# Schematic_Candy_sensor.net
KiCad netlist of a schematic drawn in EAGLE
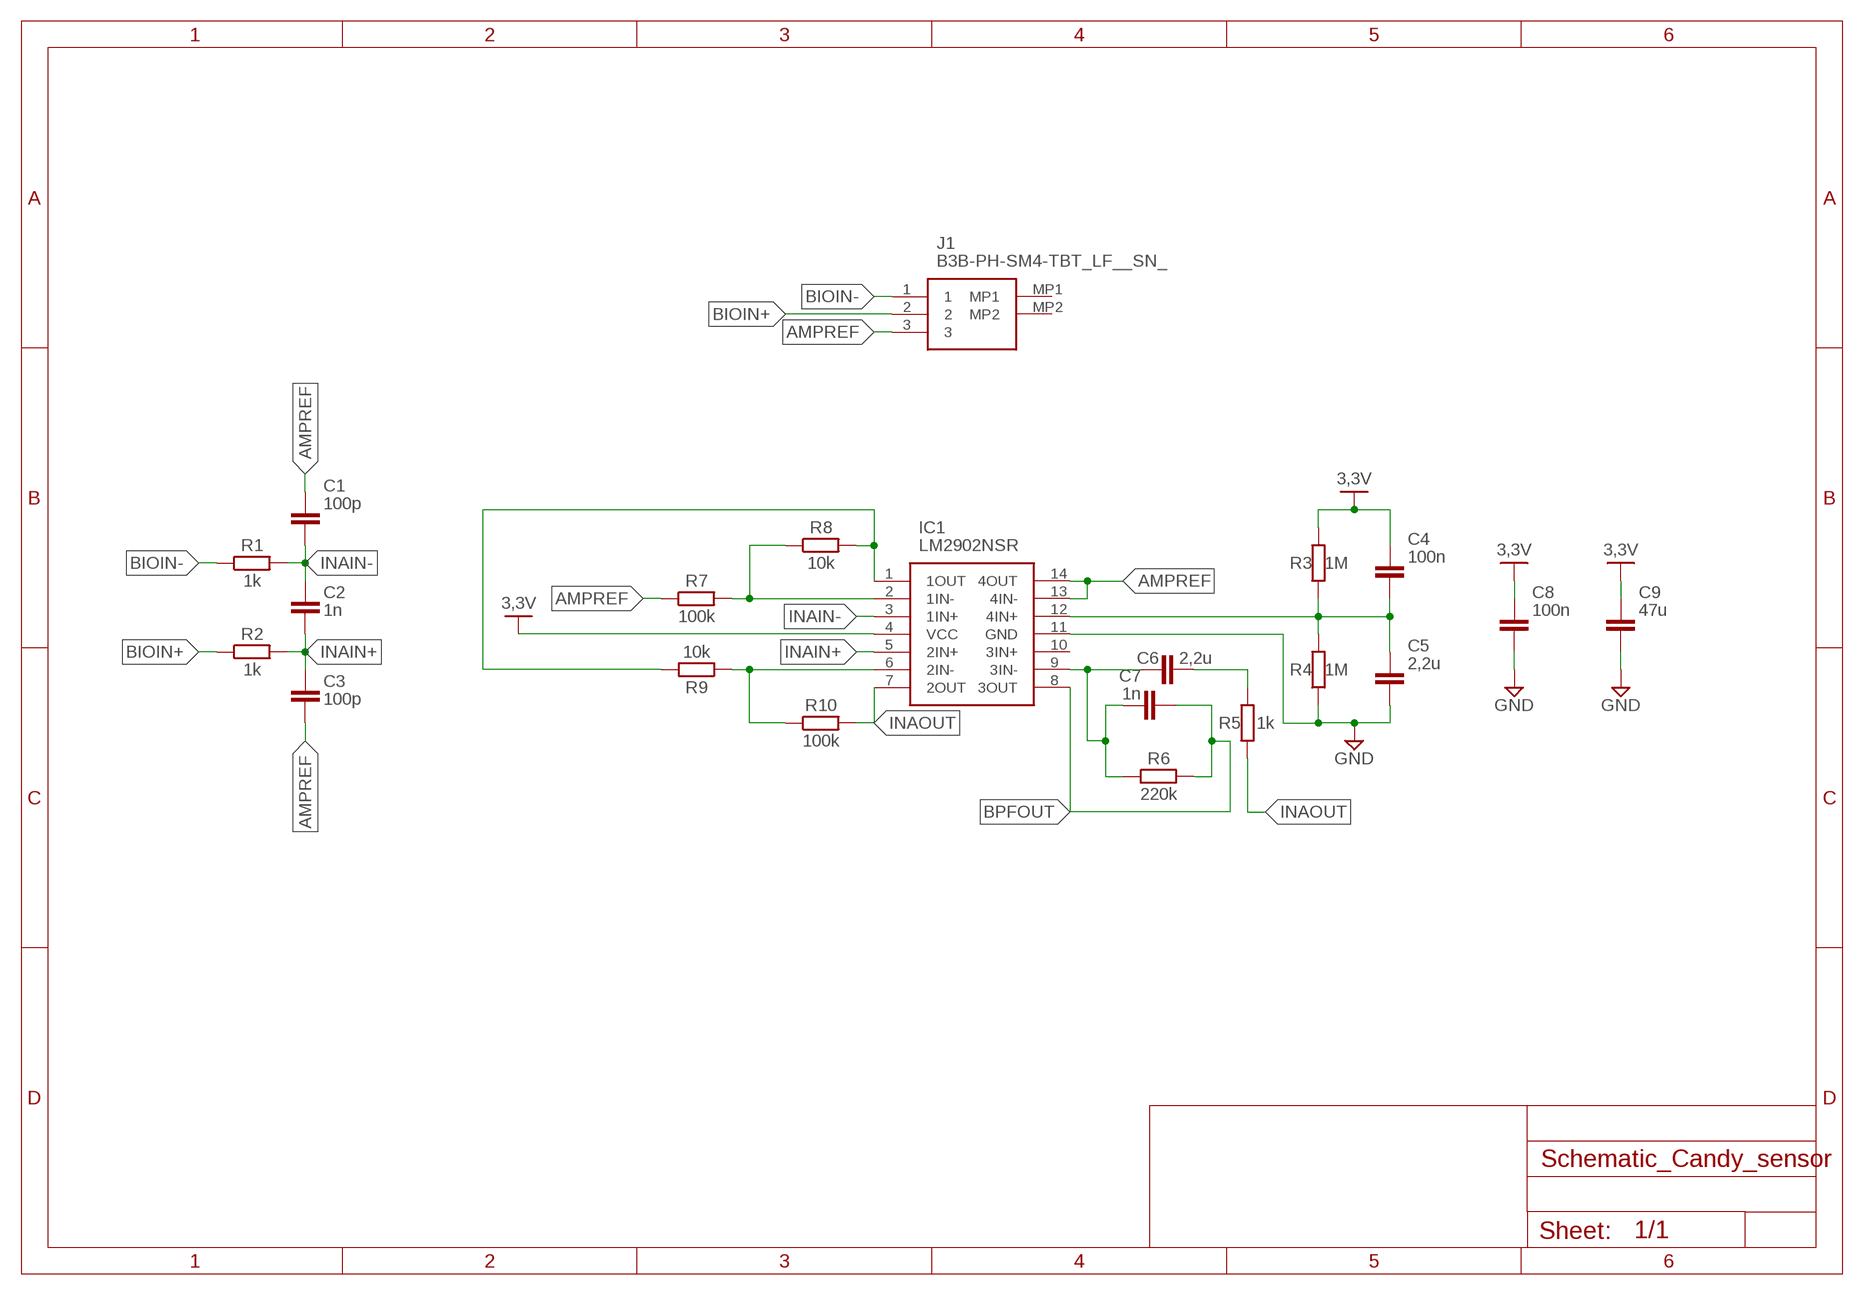
[diagram p0: schematic, sheet 1]

(export (version "E")
  (design (tool "Eeschema 10.0.6"))
  (components
    (comp (ref "C1")
      (value "100p")
      (footprint "eagle-import:CAPC2012X110")
      (libsource (lib "eagle-import") (part "CCHIP-0805(2012-METRIC)_"))
    )
    (comp (ref "C2")
      (value "1n")
      (footprint "eagle-import:CAPC2012X110")
      (libsource (lib "eagle-import") (part "CCHIP-0805(2012-METRIC)_"))
    )
    (comp (ref "C3")
      (value "100p")
      (footprint "eagle-import:CAPC2012X110")
      (libsource (lib "eagle-import") (part "CCHIP-0805(2012-METRIC)_"))
    )
    (comp (ref "C4")
      (value "100n")
      (footprint "eagle-import:CAPC2012X110")
      (libsource (lib "eagle-import") (part "CCHIP-0805(2012-METRIC)_"))
    )
    (comp (ref "C5")
      (value "2,2u")
      (footprint "eagle-import:CAPC2012X110")
      (libsource (lib "eagle-import") (part "CCHIP-0805(2012-METRIC)_"))
    )
    (comp (ref "C6")
      (value "2,2u")
      (footprint "eagle-import:CAPC2012X110")
      (libsource (lib "eagle-import") (part "CCHIP-0805(2012-METRIC)_"))
    )
    (comp (ref "C7")
      (value "1n")
      (footprint "eagle-import:CAPC2012X110")
      (libsource (lib "eagle-import") (part "CCHIP-0805(2012-METRIC)_"))
    )
    (comp (ref "C8")
      (value "100n")
      (footprint "eagle-import:CAPC2012X110")
      (libsource (lib "eagle-import") (part "CCHIP-0805(2012-METRIC)_"))
    )
    (comp (ref "C9")
      (value "47u")
      (footprint "eagle-import:CAPC2012X110")
      (libsource (lib "eagle-import") (part "CCHIP-0805(2012-METRIC)_"))
    )
    (comp (ref "IC1")
      (value "LM2902NSR")
      (footprint "eagle-import:SOIC127P780X200-14N")
      (fields (field (name "MOUSER_PART_NUMBER") "595-LM2902NSR"))
      (libsource (lib "eagle-import") (part "LM2902NSR"))
    )
    (comp (ref "J1")
      (value "B3B-PH-SM4-TBT_LF__SN_")
      (footprint "eagle-import:B3BPHSM4TBTLFSN")
      (fields (field (name "MANUFACTURER_PART_NUMBER") "B3B-PH-SM4-TBT(LF)(SN)"))
      (libsource (lib "eagle-import") (part "B3B-PH-SM4-TBT_LF__SN_"))
    )
    (comp (ref "R1")
      (value "1k")
      (footprint "eagle-import:RESC2012X65")
      (libsource (lib "eagle-import") (part "RCHIP-0805(2012-METRIC)_"))
    )
    (comp (ref "R2")
      (value "1k")
      (footprint "eagle-import:RESC2012X65")
      (libsource (lib "eagle-import") (part "RCHIP-0805(2012-METRIC)_"))
    )
    (comp (ref "R3")
      (value "1M")
      (footprint "eagle-import:RESC2012X65")
      (libsource (lib "eagle-import") (part "RCHIP-0805(2012-METRIC)_"))
    )
    (comp (ref "R4")
      (value "1M")
      (footprint "eagle-import:RESC2012X65")
      (libsource (lib "eagle-import") (part "RCHIP-0805(2012-METRIC)_"))
    )
    (comp (ref "R5")
      (value "1k")
      (footprint "eagle-import:RESC2012X65")
      (libsource (lib "eagle-import") (part "RCHIP-0805(2012-METRIC)_"))
    )
    (comp (ref "R6")
      (value "220k")
      (footprint "eagle-import:RESC2012X65")
      (libsource (lib "eagle-import") (part "RCHIP-0805(2012-METRIC)_"))
    )
    (comp (ref "R7")
      (value "100k")
      (footprint "eagle-import:RESC2012X65")
      (libsource (lib "eagle-import") (part "RCHIP-0805(2012-METRIC)_"))
    )
    (comp (ref "R8")
      (value "10k")
      (footprint "eagle-import:RESC2012X65")
      (libsource (lib "eagle-import") (part "RCHIP-0805(2012-METRIC)_"))
    )
    (comp (ref "R9")
      (value "10k")
      (footprint "eagle-import:RESC2012X65")
      (libsource (lib "eagle-import") (part "RCHIP-0805(2012-METRIC)_"))
    )
    (comp (ref "R10")
      (value "100k")
      (footprint "eagle-import:RESC2012X65")
      (libsource (lib "eagle-import") (part "RCHIP-0805(2012-METRIC)_"))
    )
  )
  (nets
    (net (code "1") (name "3,3V") (class "Default")
      (node (ref "C4") (pin "1") (pinfunction "1_1") (pintype "passive"))
      (node (ref "C8") (pin "1") (pinfunction "1_1") (pintype "passive"))
      (node (ref "C9") (pin "1") (pinfunction "1_1") (pintype "passive"))
      (node (ref "IC1") (pin "4") (pinfunction "VCC_4") (pintype "bidirectional"))
      (node (ref "R3") (pin "2") (pinfunction "2_2") (pintype "passive"))
    )
    (net (code "2") (name "AMPREF") (class "Default")
      (node (ref "C1") (pin "1") (pinfunction "1_1") (pintype "passive"))
      (node (ref "C3") (pin "2") (pinfunction "2_2") (pintype "passive"))
      (node (ref "IC1") (pin "13") (pinfunction "4IN-_13") (pintype "bidirectional"))
      (node (ref "IC1") (pin "14") (pinfunction "4OUT_14") (pintype "bidirectional"))
      (node (ref "J1") (pin "3") (pinfunction "3_3") (pintype "bidirectional"))
      (node (ref "R7") (pin "1") (pinfunction "1_1") (pintype "passive"))
    )
    (net (code "3") (name "BIOIN+") (class "Default")
      (node (ref "J1") (pin "2") (pinfunction "2_2") (pintype "bidirectional"))
      (node (ref "R2") (pin "1") (pinfunction "1_1") (pintype "passive"))
    )
    (net (code "4") (name "BIOIN-") (class "Default")
      (node (ref "J1") (pin "1") (pinfunction "1_1") (pintype "bidirectional"))
      (node (ref "R1") (pin "1") (pinfunction "1_1") (pintype "passive"))
    )
    (net (code "5") (name "BPFOUT") (class "Default")
      (node (ref "C7") (pin "2") (pinfunction "2_2") (pintype "passive"))
      (node (ref "IC1") (pin "8") (pinfunction "3OUT_8") (pintype "bidirectional"))
      (node (ref "R6") (pin "2") (pinfunction "2_2") (pintype "passive"))
    )
    (net (code "6") (name "GND") (class "Default")
      (node (ref "C5") (pin "2") (pinfunction "2_2") (pintype "passive"))
      (node (ref "C8") (pin "2") (pinfunction "2_2") (pintype "passive"))
      (node (ref "C9") (pin "2") (pinfunction "2_2") (pintype "passive"))
      (node (ref "IC1") (pin "11") (pinfunction "GND_11") (pintype "bidirectional"))
      (node (ref "R4") (pin "1") (pinfunction "1_1") (pintype "passive"))
    )
    (net (code "7") (name "INAIN+") (class "Default")
      (node (ref "C2") (pin "2") (pinfunction "2_2") (pintype "passive"))
      (node (ref "C3") (pin "1") (pinfunction "1_1") (pintype "passive"))
      (node (ref "IC1") (pin "5") (pinfunction "2IN+_5") (pintype "bidirectional"))
      (node (ref "R2") (pin "2") (pinfunction "2_2") (pintype "passive"))
    )
    (net (code "8") (name "INAIN-") (class "Default")
      (node (ref "C1") (pin "2") (pinfunction "2_2") (pintype "passive"))
      (node (ref "C2") (pin "1") (pinfunction "1_1") (pintype "passive"))
      (node (ref "IC1") (pin "3") (pinfunction "1IN+_3") (pintype "bidirectional"))
      (node (ref "R1") (pin "2") (pinfunction "2_2") (pintype "passive"))
    )
    (net (code "9") (name "INAOUT") (class "Default")
      (node (ref "IC1") (pin "7") (pinfunction "2OUT_7") (pintype "bidirectional"))
      (node (ref "R10") (pin "2") (pinfunction "2_2") (pintype "passive"))
      (node (ref "R5") (pin "1") (pinfunction "1_1") (pintype "passive"))
    )
    (net (code "10") (name "Net-(C6-Pad2)") (class "Default")
      (node (ref "C6") (pin "2") (pinfunction "2_2") (pintype "passive"))
      (node (ref "R5") (pin "2") (pinfunction "2_2") (pintype "passive"))
    )
    (net (code "11") (name "Net-(IC1-1IN-)") (class "Default")
      (node (ref "IC1") (pin "2") (pinfunction "1IN-_2") (pintype "bidirectional"))
      (node (ref "R7") (pin "2") (pinfunction "2_2") (pintype "passive"))
      (node (ref "R8") (pin "1") (pinfunction "1_1") (pintype "passive"))
    )
    (net (code "12") (name "Net-(IC1-1OUT)") (class "Default")
      (node (ref "IC1") (pin "1") (pinfunction "1OUT_1") (pintype "bidirectional"))
      (node (ref "R8") (pin "2") (pinfunction "2_2") (pintype "passive"))
      (node (ref "R9") (pin "2") (pinfunction "2_2") (pintype "passive"))
    )
    (net (code "13") (name "Net-(IC1-2IN-)") (class "Default")
      (node (ref "IC1") (pin "6") (pinfunction "2IN-_6") (pintype "bidirectional"))
      (node (ref "R10") (pin "1") (pinfunction "1_1") (pintype "passive"))
      (node (ref "R9") (pin "1") (pinfunction "1_1") (pintype "passive"))
    )
    (net (code "14") (name "Net-(IC1-3IN-)") (class "Default")
      (node (ref "C6") (pin "1") (pinfunction "1_1") (pintype "passive"))
      (node (ref "C7") (pin "1") (pinfunction "1_1") (pintype "passive"))
      (node (ref "IC1") (pin "9") (pinfunction "3IN-_9") (pintype "bidirectional"))
      (node (ref "R6") (pin "1") (pinfunction "1_1") (pintype "passive"))
    )
    (net (code "15") (name "Net-(IC1-4IN+)") (class "Default")
      (node (ref "C4") (pin "2") (pinfunction "2_2") (pintype "passive"))
      (node (ref "C5") (pin "1") (pinfunction "1_1") (pintype "passive"))
      (node (ref "IC1") (pin "12") (pinfunction "4IN+_12") (pintype "bidirectional"))
      (node (ref "R3") (pin "1") (pinfunction "1_1") (pintype "passive"))
      (node (ref "R4") (pin "2") (pinfunction "2_2") (pintype "passive"))
    )
    (net (code "16") (name "unconnected-(IC1-3IN+-Pad10)") (class "Default")
      (node (ref "IC1") (pin "10") (pinfunction "3IN+_10") (pintype "bidirectional"))
    )
    (net (code "17") (name "unconnected-(J1-PadMP1)") (class "Default")
      (node (ref "J1") (pin "MP1") (pinfunction "MP1_MP1") (pintype "bidirectional"))
    )
    (net (code "18") (name "unconnected-(J1-PadMP2)") (class "Default")
      (node (ref "J1") (pin "MP2") (pinfunction "MP2_MP2") (pintype "bidirectional"))
    )
  )
)
